# Power.net
KiCad netlist of a schematic drawn in Altium Designer
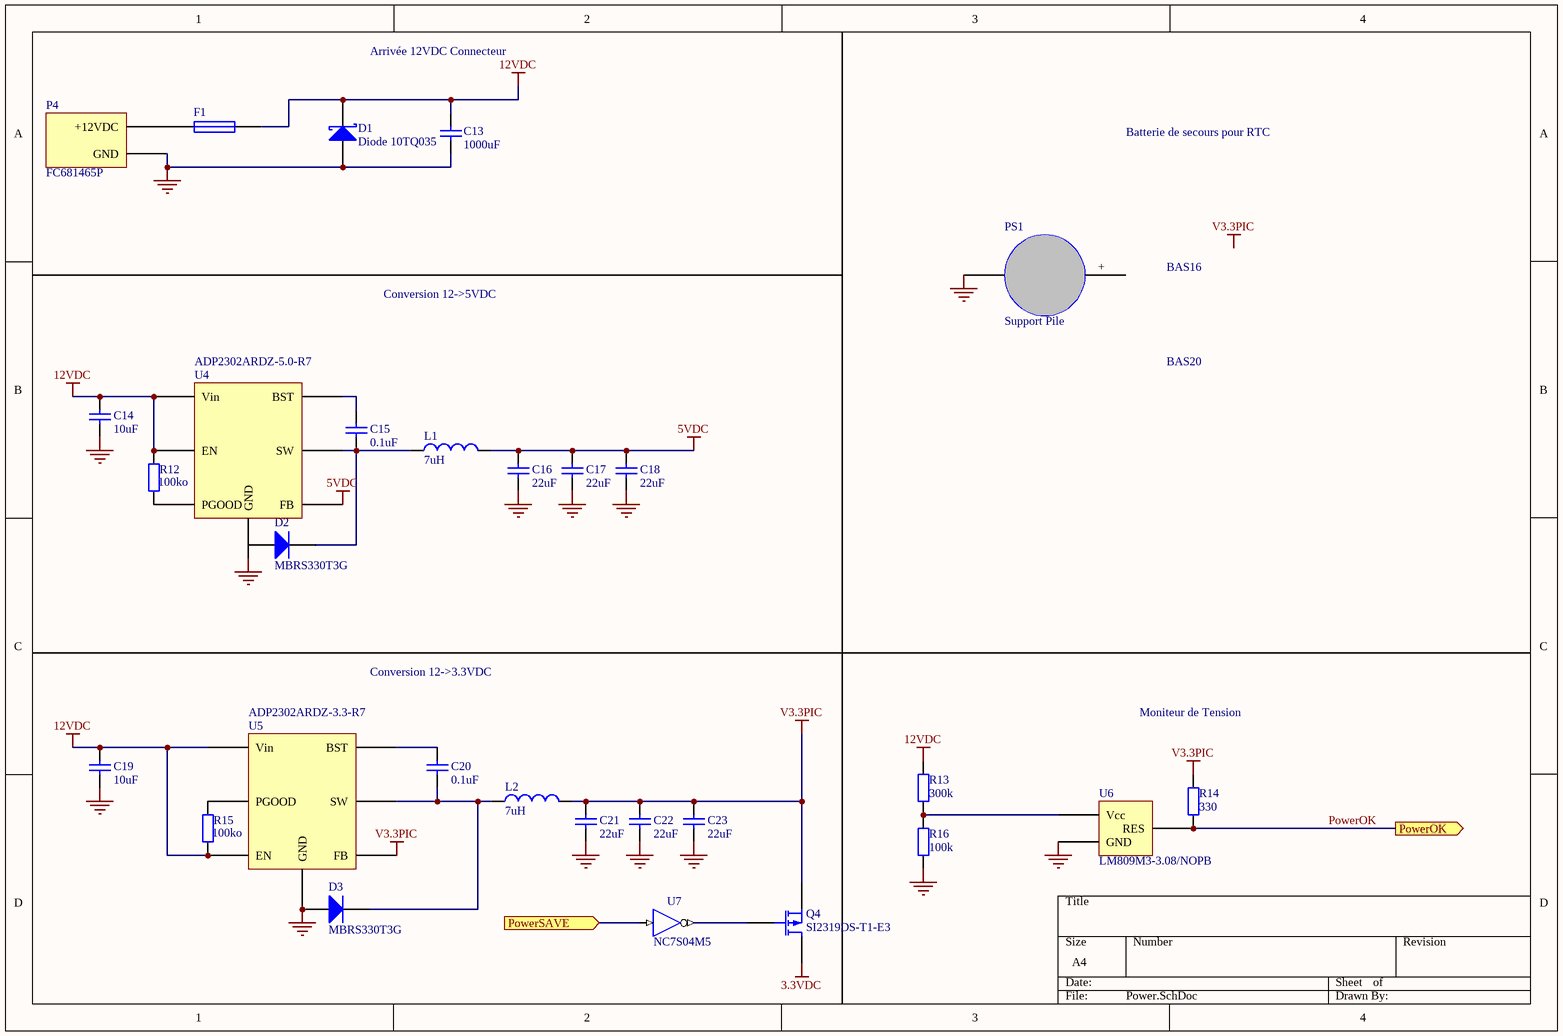
[diagram p0: Power.SchDoc]

(export (version "E")
  (design (tool "Eeschema 10.0.6"))
  (components
    (comp (ref "C13")
      (value "1000uF")
      (footprint "RAD-0.3")
      (description "Capacitor")
      (libsource (lib "Miscellaneous Devices") (part "Cap"))
    )
    (comp (ref "C14")
      (value "10uF")
      (footprint "RAD-0.3")
      (description "Cin_Reg_5v")
      (libsource (lib "Miscellaneous Devices") (part "Cap"))
    )
    (comp (ref "C15")
      (value "0.1uF")
      (footprint "RAD-0.3")
      (description "Cbst_Reg_5v")
      (libsource (lib "Miscellaneous Devices") (part "Cap"))
    )
    (comp (ref "C16")
      (value "22uF")
      (footprint "RAD-0.3")
      (description "Cout_Reg_3.3v")
      (libsource (lib "Miscellaneous Devices") (part "Cap"))
    )
    (comp (ref "C17")
      (value "22uF")
      (footprint "RAD-0.3")
      (description "Cout_Reg_3.3v")
      (libsource (lib "Miscellaneous Devices") (part "Cap"))
    )
    (comp (ref "C18")
      (value "22uF")
      (footprint "RAD-0.3")
      (description "Cout_Reg_3.3v")
      (libsource (lib "Miscellaneous Devices") (part "Cap"))
    )
    (comp (ref "C19")
      (value "10uF")
      (footprint "RAD-0.3")
      (description "Cin_Reg_3v")
      (libsource (lib "Miscellaneous Devices") (part "Cap"))
    )
    (comp (ref "C20")
      (value "0.1uF")
      (footprint "RAD-0.3")
      (description "Cbst_Reg_3.3v")
      (libsource (lib "Miscellaneous Devices") (part "Cap"))
    )
    (comp (ref "C21")
      (value "22uF")
      (footprint "RAD-0.3")
      (description "Cout_Reg_3.3v")
      (libsource (lib "Miscellaneous Devices") (part "Cap"))
    )
    (comp (ref "C22")
      (value "22uF")
      (footprint "RAD-0.3")
      (description "Cout_Reg_3.3v")
      (libsource (lib "Miscellaneous Devices") (part "Cap"))
    )
    (comp (ref "C23")
      (value "22uF")
      (footprint "RAD-0.3")
      (description "Cout_Reg_3.3v")
      (libsource (lib "Miscellaneous Devices") (part "Cap"))
    )
    (comp (ref "D1")
      (value "Diode 10TQ035")
      (footprint "TO-220AC")
      (description "Diode Zenner")
      (libsource (lib "Miscellaneous Devices") (part "Diode 10TQ035"))
    )
    (comp (ref "D2")
      (value "MBRS330T3G")
      (footprint "SMC")
      (description "Schottky")
      (libsource (lib "Miscellaneous Devices") (part "Diode"))
    )
    (comp (ref "D3")
      (value "MBRS330T3G")
      (footprint "SMC")
      (description "Schottky")
      (libsource (lib "Miscellaneous Devices") (part "Diode"))
    )
    (comp (ref "F1")
      (value "Fuse 1")
      (footprint "PIN-W2/E2.8")
      (description "Fuse")
      (libsource (lib "Miscellaneous Devices") (part "Fuse 1"))
    )
    (comp (ref "L1")
      (value "7uH")
      (footprint "0402-A")
      (description "L_Reg_5v")
      (libsource (lib "Miscellaneous Devices") (part "Inductor"))
    )
    (comp (ref "L2")
      (value "7uH")
      (footprint "0402-A")
      (description "L_Reg_3.3v")
      (libsource (lib "Miscellaneous Devices") (part "Inductor"))
    )
    (comp (ref "P4")
      (value "FC681465P")
      (description "Power connector")
      (libsource (lib "Schlib1") (part "FC68148S"))
    )
    (comp (ref "PS1") (value "Support Pile") (libsource (lib "Schlib1") (part "SMTU-1225-1-LF")))
    (comp (ref "Q4")
      (value "SI2319DS-T1-E3")
      (footprint "E3")
      (description "P-Channel MOSFET")
      (libsource (lib "Miscellaneous Devices") (part "MOSFET-P"))
    )
    (comp (ref "R12")
      (value "100ko")
      (footprint "AXIAL-0.4")
      (description "Resistor")
      (libsource (lib "Miscellaneous Devices") (part "Res2"))
    )
    (comp (ref "R13")
      (value "300k")
      (footprint "AXIAL-0.4")
      (description "Resistor")
      (libsource (lib "Miscellaneous Devices") (part "Res2"))
    )
    (comp (ref "R14")
      (value "330")
      (footprint "AXIAL-0.4")
      (description "Resistor")
      (libsource (lib "Miscellaneous Devices") (part "Res2"))
    )
    (comp (ref "R15")
      (value "100ko")
      (footprint "AXIAL-0.4")
      (description "Resistor")
      (libsource (lib "Miscellaneous Devices") (part "Res2"))
    )
    (comp (ref "R16")
      (value "100k")
      (footprint "AXIAL-0.4")
      (description "Resistor")
      (libsource (lib "Miscellaneous Devices") (part "Res2"))
    )
    (comp (ref "U4")
      (value "ADP2302ARDZ-5.0-R7")
      (description "Convert. 5v")
      (libsource (lib "Schlib1") (part "ADP2302ARDZ-5.0-R7"))
    )
    (comp (ref "U5")
      (value "ADP2302ARDZ-3.3-R7")
      (description "Convert.3.3")
      (libsource (lib "Schlib1") (part "ADP2302ARDZ-3.3-R7"))
    )
    (comp (ref "U6")
      (value "LM809M3-3.08/NOPB")
      (description "Voltage Monitor")
      (libsource (lib "Schlib1") (part "LM809M3-3.08/NOPB"))
    )
    (comp (ref "U7")
      (value "NC7S04M5")
      (description "Inverter")
      (libsource (lib "FPGA Generic") (part "INV"))
    )
  )
  (nets
    (net (code "1") (name "/PowerOK") (class "Default")
      (node (ref "R14") (pin "1") (pinfunction "1_1") (pintype "passive"))
      (node (ref "U6") (pin "RES") (pinfunction "RES_RES") (pintype "passive"))
    )
    (net (code "2") (name "/PowerSAVE") (class "Default")
      (node (ref "U7") (pin "I") (pinfunction "I_I") (pintype "input"))
    )
    (net (code "3") (name "3.3VDC") (class "Default")
      (node (ref "Q4") (pin "1") (pinfunction "D_1") (pintype "passive"))
    )
    (net (code "4") (name "5VDC") (class "Default")
      (node (ref "C16") (pin "1") (pinfunction "1_1") (pintype "passive"))
      (node (ref "C17") (pin "1") (pinfunction "1_1") (pintype "passive"))
      (node (ref "C18") (pin "1") (pinfunction "1_1") (pintype "passive"))
      (node (ref "L1") (pin "2") (pinfunction "2_2") (pintype "passive"))
      (node (ref "U4") (pin "FB") (pinfunction "FB_FB") (pintype "passive"))
    )
    (net (code "5") (name "12VDC") (class "Default")
      (node (ref "C13") (pin "2") (pinfunction "2_2") (pintype "passive"))
      (node (ref "C14") (pin "1") (pinfunction "1_1") (pintype "passive"))
      (node (ref "C19") (pin "1") (pinfunction "1_1") (pintype "passive"))
      (node (ref "D1") (pin "1") (pinfunction "K_1") (pintype "passive"))
      (node (ref "F1") (pin "2") (pinfunction "2_2") (pintype "passive"))
      (node (ref "R12") (pin "2") (pinfunction "2_2") (pintype "passive"))
      (node (ref "R13") (pin "2") (pinfunction "2_2") (pintype "passive"))
      (node (ref "R15") (pin "1") (pinfunction "1_1") (pintype "passive"))
      (node (ref "U4") (pin "EN") (pinfunction "EN_EN") (pintype "passive"))
      (node (ref "U4") (pin "Vin") (pinfunction "Vin_Vin") (pintype "passive"))
      (node (ref "U5") (pin "EN") (pinfunction "EN_EN") (pintype "passive"))
      (node (ref "U5") (pin "Vin") (pinfunction "Vin_Vin") (pintype "passive"))
    )
    (net (code "6") (name "GND") (class "Default")
      (node (ref "C13") (pin "1") (pinfunction "1_1") (pintype "passive"))
      (node (ref "C14") (pin "2") (pinfunction "2_2") (pintype "passive"))
      (node (ref "C16") (pin "2") (pinfunction "2_2") (pintype "passive"))
      (node (ref "C17") (pin "2") (pinfunction "2_2") (pintype "passive"))
      (node (ref "C18") (pin "2") (pinfunction "2_2") (pintype "passive"))
      (node (ref "C19") (pin "2") (pinfunction "2_2") (pintype "passive"))
      (node (ref "C21") (pin "2") (pinfunction "2_2") (pintype "passive"))
      (node (ref "C22") (pin "2") (pinfunction "2_2") (pintype "passive"))
      (node (ref "C23") (pin "2") (pinfunction "2_2") (pintype "passive"))
      (node (ref "D1") (pin "3") (pinfunction "A_3") (pintype "passive"))
      (node (ref "D3") (pin "1") (pinfunction "A_1") (pintype "passive"))
      (node (ref "P4") (pin "GND") (pinfunction "GND_GND") (pintype "passive"))
      (node (ref "PS1") (pin "-") (pinfunction "-_-") (pintype "passive"))
      (node (ref "R16") (pin "1") (pinfunction "1_1") (pintype "passive"))
      (node (ref "U4") (pin "GND") (pinfunction "GND_GND") (pintype "passive"))
      (node (ref "U5") (pin "GND") (pinfunction "GND_GND") (pintype "passive"))
      (node (ref "U6") (pin "GND") (pinfunction "GND_GND") (pintype "passive"))
    )
    (net (code "7") (name "Net-(C15-Pad1)") (class "Default")
      (node (ref "C15") (pin "1") (pinfunction "1_1") (pintype "passive"))
      (node (ref "U4") (pin "BST") (pinfunction "BST_BST") (pintype "passive"))
    )
    (net (code "8") (name "Net-(C20-Pad1)") (class "Default")
      (node (ref "C20") (pin "1") (pinfunction "1_1") (pintype "passive"))
      (node (ref "U5") (pin "BST") (pinfunction "BST_BST") (pintype "passive"))
    )
    (net (code "9") (name "Net-(D2-K)") (class "Default")
      (node (ref "C15") (pin "2") (pinfunction "2_2") (pintype "passive"))
      (node (ref "D2") (pin "2") (pinfunction "K_2") (pintype "passive"))
      (node (ref "L1") (pin "1") (pinfunction "1_1") (pintype "passive"))
      (node (ref "U4") (pin "SW") (pinfunction "SW_SW") (pintype "passive"))
    )
    (net (code "10") (name "Net-(D3-K)") (class "Default")
      (node (ref "C20") (pin "2") (pinfunction "2_2") (pintype "passive"))
      (node (ref "D3") (pin "2") (pinfunction "K_2") (pintype "passive"))
      (node (ref "L2") (pin "1") (pinfunction "1_1") (pintype "passive"))
      (node (ref "U5") (pin "SW") (pinfunction "SW_SW") (pintype "passive"))
    )
    (net (code "11") (name "Net-(F1-Pad1)") (class "Default")
      (node (ref "F1") (pin "1") (pinfunction "1_1") (pintype "passive"))
      (node (ref "P4") (pin "+12VDC") (pinfunction "+12VDC_+12VDC") (pintype "passive"))
    )
    (net (code "12") (name "Net-(Q4-G)") (class "Default")
      (node (ref "Q4") (pin "2") (pinfunction "G_2") (pintype "passive"))
      (node (ref "U7") (pin "O") (pinfunction "O_O") (pintype "output"))
    )
    (net (code "13") (name "Net-(R12-Pad1)") (class "Default")
      (node (ref "R12") (pin "1") (pinfunction "1_1") (pintype "passive"))
      (node (ref "U4") (pin "PGOOD") (pinfunction "PGOOD_PGOOD") (pintype "passive"))
    )
    (net (code "14") (name "Net-(R13-Pad1)") (class "Default")
      (node (ref "R13") (pin "1") (pinfunction "1_1") (pintype "passive"))
      (node (ref "R16") (pin "2") (pinfunction "2_2") (pintype "passive"))
      (node (ref "U6") (pin "Vcc") (pinfunction "Vcc_Vcc") (pintype "passive"))
    )
    (net (code "15") (name "Net-(R15-Pad2)") (class "Default")
      (node (ref "R15") (pin "2") (pinfunction "2_2") (pintype "passive"))
      (node (ref "U5") (pin "PGOOD") (pinfunction "PGOOD_PGOOD") (pintype "passive"))
    )
    (net (code "16") (name "V3.3PIC") (class "Default")
      (node (ref "C21") (pin "1") (pinfunction "1_1") (pintype "passive"))
      (node (ref "C22") (pin "1") (pinfunction "1_1") (pintype "passive"))
      (node (ref "C23") (pin "1") (pinfunction "1_1") (pintype "passive"))
      (node (ref "L2") (pin "2") (pinfunction "2_2") (pintype "passive"))
      (node (ref "Q4") (pin "3") (pinfunction "S_3") (pintype "passive"))
      (node (ref "R14") (pin "2") (pinfunction "2_2") (pintype "passive"))
      (node (ref "U5") (pin "FB") (pinfunction "FB_FB") (pintype "passive"))
    )
    (net (code "17") (name "unconnected-(D2-A-Pad1)") (class "Default")
      (node (ref "D2") (pin "1") (pinfunction "A_1") (pintype "passive"))
    )
    (net (code "18") (name "unconnected-(PS1-Pad+)") (class "Default")
      (node (ref "PS1") (pin "+") (pinfunction "+_+") (pintype "passive"))
    )
  )
)
